# 780-00036_rev2_Sch_Crate_Slot_Power_Inte.net
KiCad netlist of a schematic drawn in Altium Designer
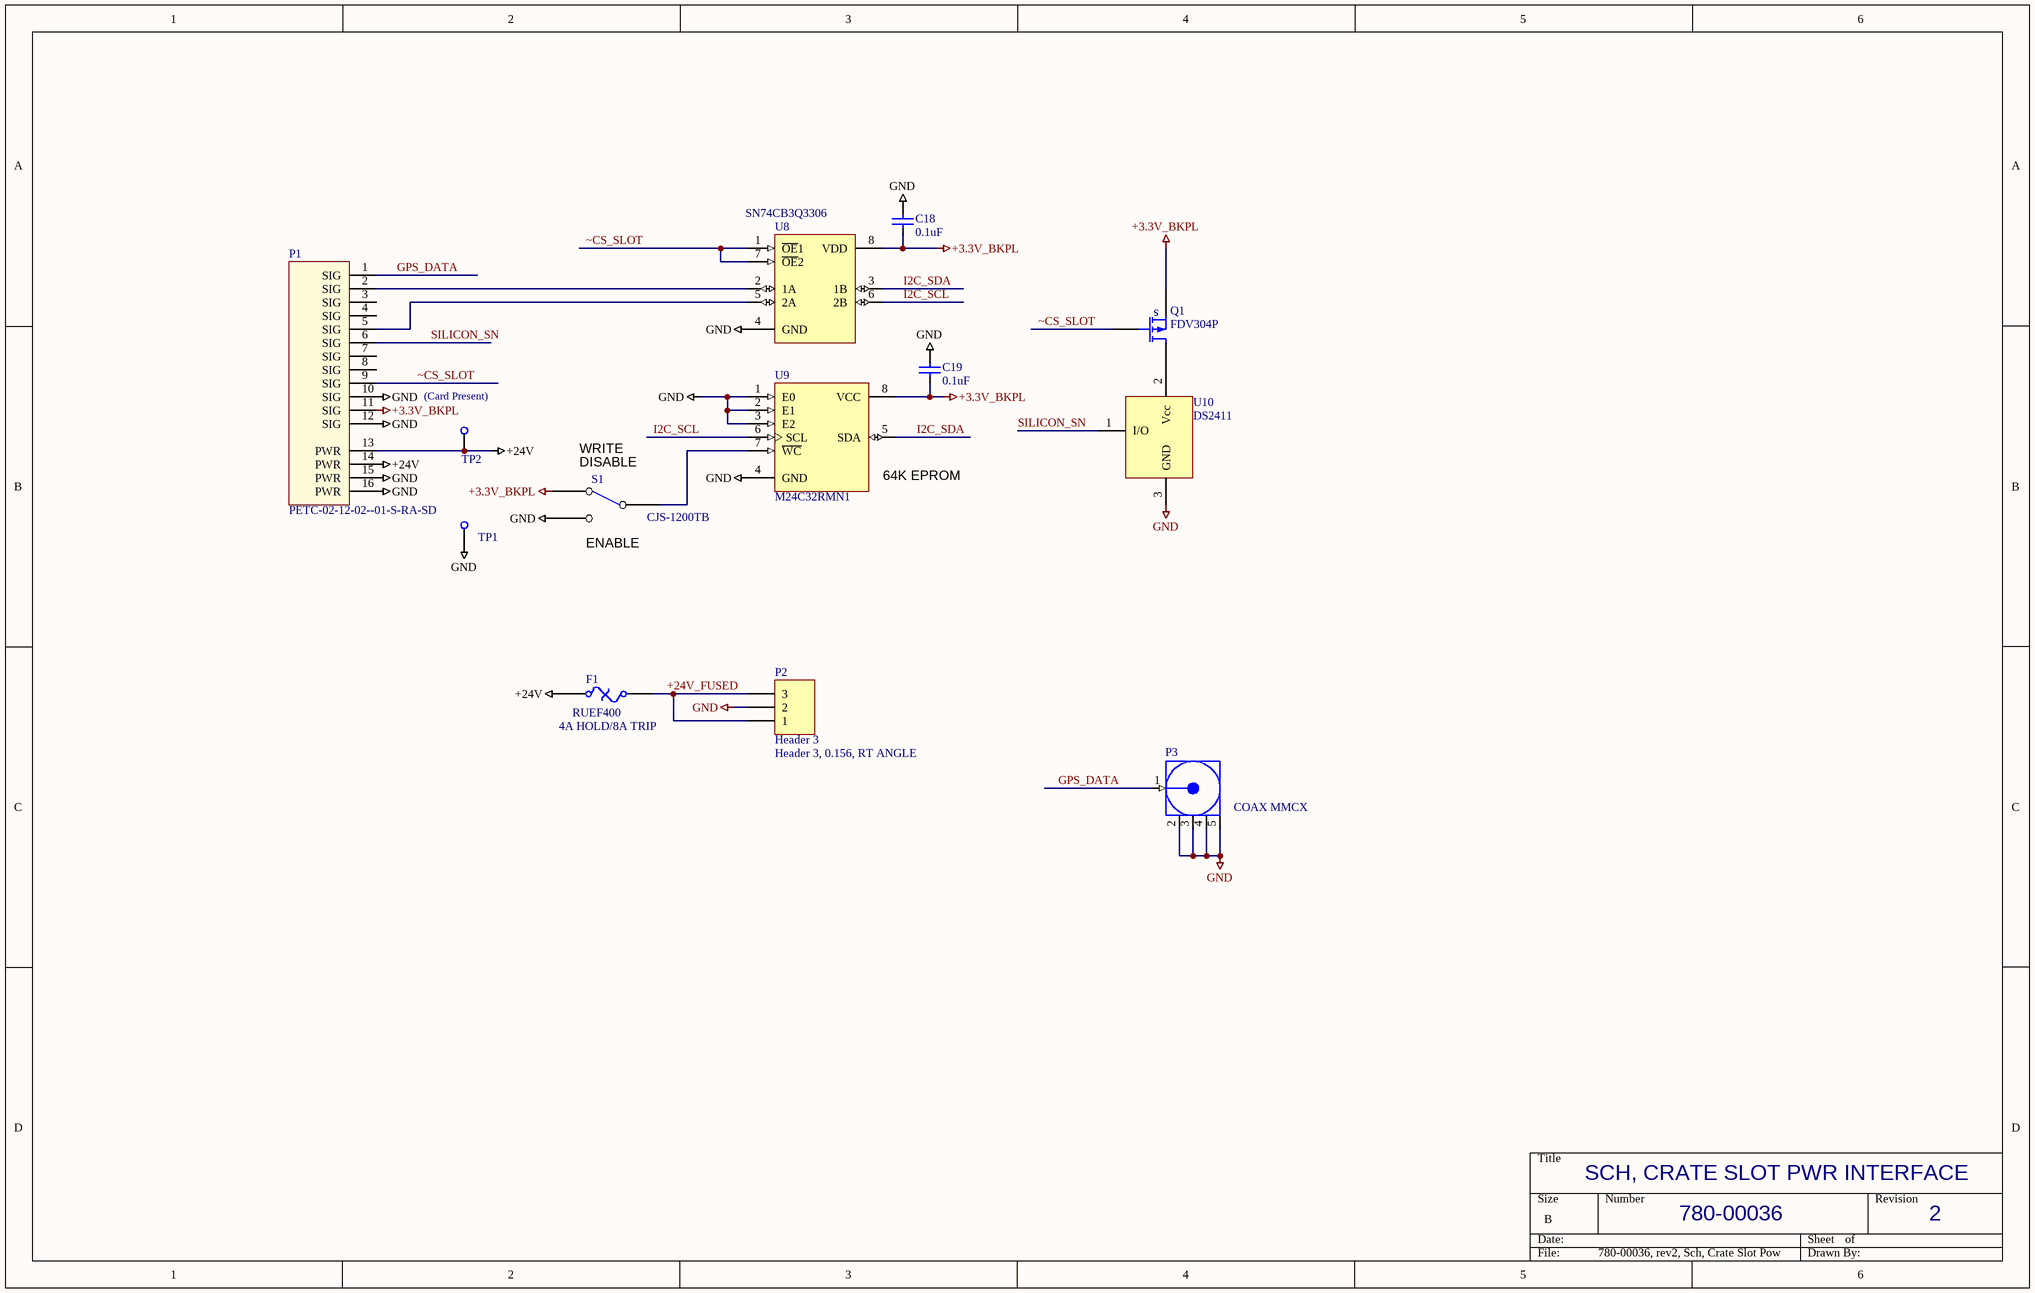
[diagram p0: 780-00036, rev2, Sch, Crate Slot Power Interface.SchDoc]

(export (version "E")
  (design (tool "Eeschema 10.0.6"))
  (components
    (comp (ref "C18")
      (value "0.1uF")
      (footprint "SMD_0805")
      (description "Capacitor")
      (fields (field (name "MANUFACTURER") "AVX") (field (name "Comment") "Cap SMD"))
      (libsource (lib "Richs Schematic Components") (part "Cap SMD"))
    )
    (comp (ref "C19")
      (value "0.1uF")
      (footprint "SMD_0805")
      (description "Capacitor")
      (fields (field (name "MANUFACTURER") "AVX") (field (name "Comment") "Cap SMD"))
      (libsource (lib "Richs Schematic Components") (part "Cap SMD"))
    )
    (comp (ref "F1")
      (value "RUEF400")
      (footprint "PolySwitch Radial 0.2")
      (description "PolySwitch RUE Series")
      (fields
        (field (name "MANUFACTURER") "Tyco Electronics")
        (field (name "ALTIUM_VALUE") "4A HOLD/8A TRIP")
      )
      (libsource (lib "Richs Schematic Components") (part "Fuse Thermal"))
    )
    (comp (ref "P1")
      (value "PETC-02-12-02--01-S-RA-SD")
      (footprint "PETC-02-12-02-01-RA")
      (description "SAMTEC, SIGNAL(12)+PWR(4)")
      (fields (field (name "MANUFACTURER") "SAMTEC"))
      (libsource (lib "Richs Schematic Components") (part "PETC-02-12-02--01-S-RA-SD"))
    )
    (comp (ref "P2")
      (value "Header 3")
      (footprint "HDR 1X3 0.156\" - RT ANGLE")
      (description "Header, 3-Pin, 0.156, RT ANGLE")
      (fields
        (field (name "MANUFACTURER") "TE Connectivity")
        (field (name "ALTIUM_VALUE") "Header 3, 0.156, RT ANGLE")
      )
      (libsource (lib "Richs Schematic Components") (part "Header 3, 0.156 RT ANGLE"))
    )
    (comp (ref "P3")
      (value "COAX MMCX")
      (footprint "Miscellaneous Connectors:MMCX2.54-V5")
      (description "RF Coaxial PCB Connector, MMCX; Thru-Hole, Vertical Mount Plug,  50 Ohm Impedance")
      (fields (field (name "MANUFACTURER") "Emerson"))
      (libsource (lib "Richs Schematic Components") (part "COAX-M"))
    )
    (comp (ref "Q1")
      (value "FDV304P")
      (footprint "SMD_SOT23_3")
      (description "P-MOSFET LOGIC LEVEL")
      (fields (field (name "MANUFACTURER") "Fairchild"))
      (libsource (lib "Richs Schematic Components") (part "FDV304P"))
    )
    (comp (ref "S1")
      (value "CJS-1200TB")
      (footprint "CAS-120B")
      (fields (field (name "MANUFACTURER") "Copal Electronics"))
      (libsource (lib "JON_1_Library") (part "SW_SPDT_DOUG"))
    )
    (comp (ref "TP1")
      (value "Test Point SMD")
      (footprint "SMD_TEST POINT")
      (description "SMD loop test point")
      (libsource (lib "Richs Schematic Components") (part "Test Point SMD"))
    )
    (comp (ref "TP2")
      (value "Test Point SMD")
      (footprint "SMD_TEST POINT")
      (description "SMD loop test point")
      (libsource (lib "Richs Schematic Components") (part "Test Point SMD"))
    )
    (comp (ref "U8")
      (value "SN74CB3Q3306")
      (footprint "PW008_N")
      (description "Dual FET Bus Switch")
      (fields (field (name "MANUFACTURER") "TI") (field (name "Comment") "SN74CBT3306PWLE"))
      (libsource (lib "TI Logic Switch") (part "SN74CBT3306PWLE"))
    )
    (comp (ref "U9")
      (value "M24C32RMN1")
      (footprint "SOP8_N")
      (description "32 Kbit Serial I²C Bus EEPROM")
      (libsource (lib "ST Memory EEPROM Serial") (part "M24C32RMN1"))
    )
    (comp (ref "U10")
      (value "DS2411")
      (footprint "SMD_SOT23_3")
      (description "Silicon Serial Number")
      (fields (field (name "MANUFACTURER") "MAXIM"))
      (libsource (lib "Richs Schematic Components") (part "DS2411"))
    )
  )
  (nets
    (net (code "1") (name "+3.3V_BKPL") (class "Default")
      (node (ref "C18") (pin "1") (pinfunction "1_1") (pintype "passive"))
      (node (ref "C19") (pin "1") (pinfunction "1_1") (pintype "passive"))
      (node (ref "P1") (pin "11") (pinfunction "SIG_11") (pintype "passive"))
      (node (ref "Q1") (pin "2") (pinfunction "S_2") (pintype "passive"))
      (node (ref "S1") (pin "3") (pinfunction "NC_3") (pintype "passive"))
      (node (ref "U8") (pin "8") (pinfunction "VDD_8") (pintype "power_in"))
      (node (ref "U9") (pin "8") (pinfunction "VCC_8") (pintype "power_in"))
    )
    (net (code "2") (name "+24V") (class "Default")
      (node (ref "F1") (pin "1") (pinfunction "1_1") (pintype "passive"))
      (node (ref "P1") (pin "13") (pinfunction "PWR_13") (pintype "passive"))
      (node (ref "P1") (pin "14") (pinfunction "PWR_14") (pintype "passive"))
      (node (ref "TP2") (pin "1") (pinfunction "TP_1") (pintype "passive"))
    )
    (net (code "3") (name "/+24V_FUSED") (class "Default")
      (node (ref "F1") (pin "2") (pinfunction "2_2") (pintype "passive"))
      (node (ref "P2") (pin "1") (pinfunction "1_1") (pintype "passive"))
      (node (ref "P2") (pin "3") (pinfunction "3_3") (pintype "passive"))
    )
    (net (code "4") (name "/GPS_DATA") (class "Default")
      (node (ref "P1") (pin "1") (pinfunction "SIG_1") (pintype "passive"))
      (node (ref "P3") (pin "1") (pinfunction "Signal_1") (pintype "input"))
    )
    (net (code "5") (name "/I2C_SCL") (class "Default")
      (node (ref "U8") (pin "6") (pinfunction "2B_6") (pintype "bidirectional"))
      (node (ref "U9") (pin "6") (pinfunction "SCL_6") (pintype "input"))
    )
    (net (code "6") (name "/I2C_SDA") (class "Default")
      (node (ref "U8") (pin "3") (pinfunction "1B_3") (pintype "bidirectional"))
      (node (ref "U9") (pin "5") (pinfunction "SDA_5") (pintype "bidirectional"))
    )
    (net (code "7") (name "/SILICON_SN") (class "Default")
      (node (ref "P1") (pin "6") (pinfunction "SIG_6") (pintype "passive"))
      (node (ref "U10") (pin "1") (pinfunction "I/O_1") (pintype "passive"))
    )
    (net (code "8") (name "/~CS_SLOT") (class "Default")
      (node (ref "P1") (pin "9") (pinfunction "SIG_9") (pintype "passive"))
      (node (ref "Q1") (pin "1") (pinfunction "G_1") (pintype "passive"))
      (node (ref "U8") (pin "1") (pinfunction "~{OE}1_1") (pintype "input"))
      (node (ref "U8") (pin "7") (pinfunction "~{OE}2_7") (pintype "input"))
    )
    (net (code "9") (name "GND") (class "Default")
      (node (ref "C18") (pin "2") (pinfunction "2_2") (pintype "passive"))
      (node (ref "C19") (pin "2") (pinfunction "2_2") (pintype "passive"))
      (node (ref "P1") (pin "10") (pinfunction "SIG_10") (pintype "passive"))
      (node (ref "P1") (pin "12") (pinfunction "SIG_12") (pintype "passive"))
      (node (ref "P1") (pin "15") (pinfunction "PWR_15") (pintype "passive"))
      (node (ref "P1") (pin "16") (pinfunction "PWR_16") (pintype "passive"))
      (node (ref "P2") (pin "2") (pinfunction "2_2") (pintype "passive"))
      (node (ref "P3") (pin "2") (pinfunction "GND_2") (pintype "power_in"))
      (node (ref "P3") (pin "3") (pinfunction "GND_3") (pintype "power_in"))
      (node (ref "P3") (pin "4") (pinfunction "GND_4") (pintype "power_in"))
      (node (ref "P3") (pin "5") (pinfunction "GND_5") (pintype "power_in"))
      (node (ref "S1") (pin "1") (pinfunction "NO_1") (pintype "passive"))
      (node (ref "TP1") (pin "1") (pinfunction "TP_1") (pintype "passive"))
      (node (ref "U10") (pin "3") (pinfunction "GND_3") (pintype "passive"))
      (node (ref "U8") (pin "4") (pinfunction "GND_4") (pintype "power_in"))
      (node (ref "U9") (pin "1") (pinfunction "E0_1") (pintype "input"))
      (node (ref "U9") (pin "2") (pinfunction "E1_2") (pintype "input"))
      (node (ref "U9") (pin "3") (pinfunction "E2_3") (pintype "input"))
      (node (ref "U9") (pin "4") (pinfunction "GND_4") (pintype "power_in"))
    )
    (net (code "10") (name "Net-(Q1-D)") (class "Default")
      (node (ref "Q1") (pin "3") (pinfunction "D_3") (pintype "passive"))
      (node (ref "U10") (pin "2") (pinfunction "Vcc_2") (pintype "passive"))
    )
    (net (code "11") (name "Net-(S1-COM)") (class "Default")
      (node (ref "S1") (pin "2") (pinfunction "COM_2") (pintype "passive"))
      (node (ref "U9") (pin "7") (pinfunction "~{WC}_7") (pintype "input"))
    )
    (net (code "12") (name "Net-(U8-1A)") (class "Default")
      (node (ref "P1") (pin "2") (pinfunction "SIG_2") (pintype "passive"))
      (node (ref "U8") (pin "2") (pinfunction "1A_2") (pintype "bidirectional"))
    )
    (net (code "13") (name "Net-(U8-2A)") (class "Default")
      (node (ref "P1") (pin "5") (pinfunction "SIG_5") (pintype "passive"))
      (node (ref "U8") (pin "5") (pinfunction "2A_5") (pintype "bidirectional"))
    )
    (net (code "14") (name "unconnected-(P1-SIG-Pad3)") (class "Default")
      (node (ref "P1") (pin "3") (pinfunction "SIG_3") (pintype "passive"))
    )
    (net (code "15") (name "unconnected-(P1-SIG-Pad4)") (class "Default")
      (node (ref "P1") (pin "4") (pinfunction "SIG_4") (pintype "passive"))
    )
    (net (code "16") (name "unconnected-(P1-SIG-Pad7)") (class "Default")
      (node (ref "P1") (pin "7") (pinfunction "SIG_7") (pintype "passive"))
    )
    (net (code "17") (name "unconnected-(P1-SIG-Pad8)") (class "Default")
      (node (ref "P1") (pin "8") (pinfunction "SIG_8") (pintype "passive"))
    )
  )
)
